# DSPclk.net
KiCad netlist of a schematic drawn in Altium Designer
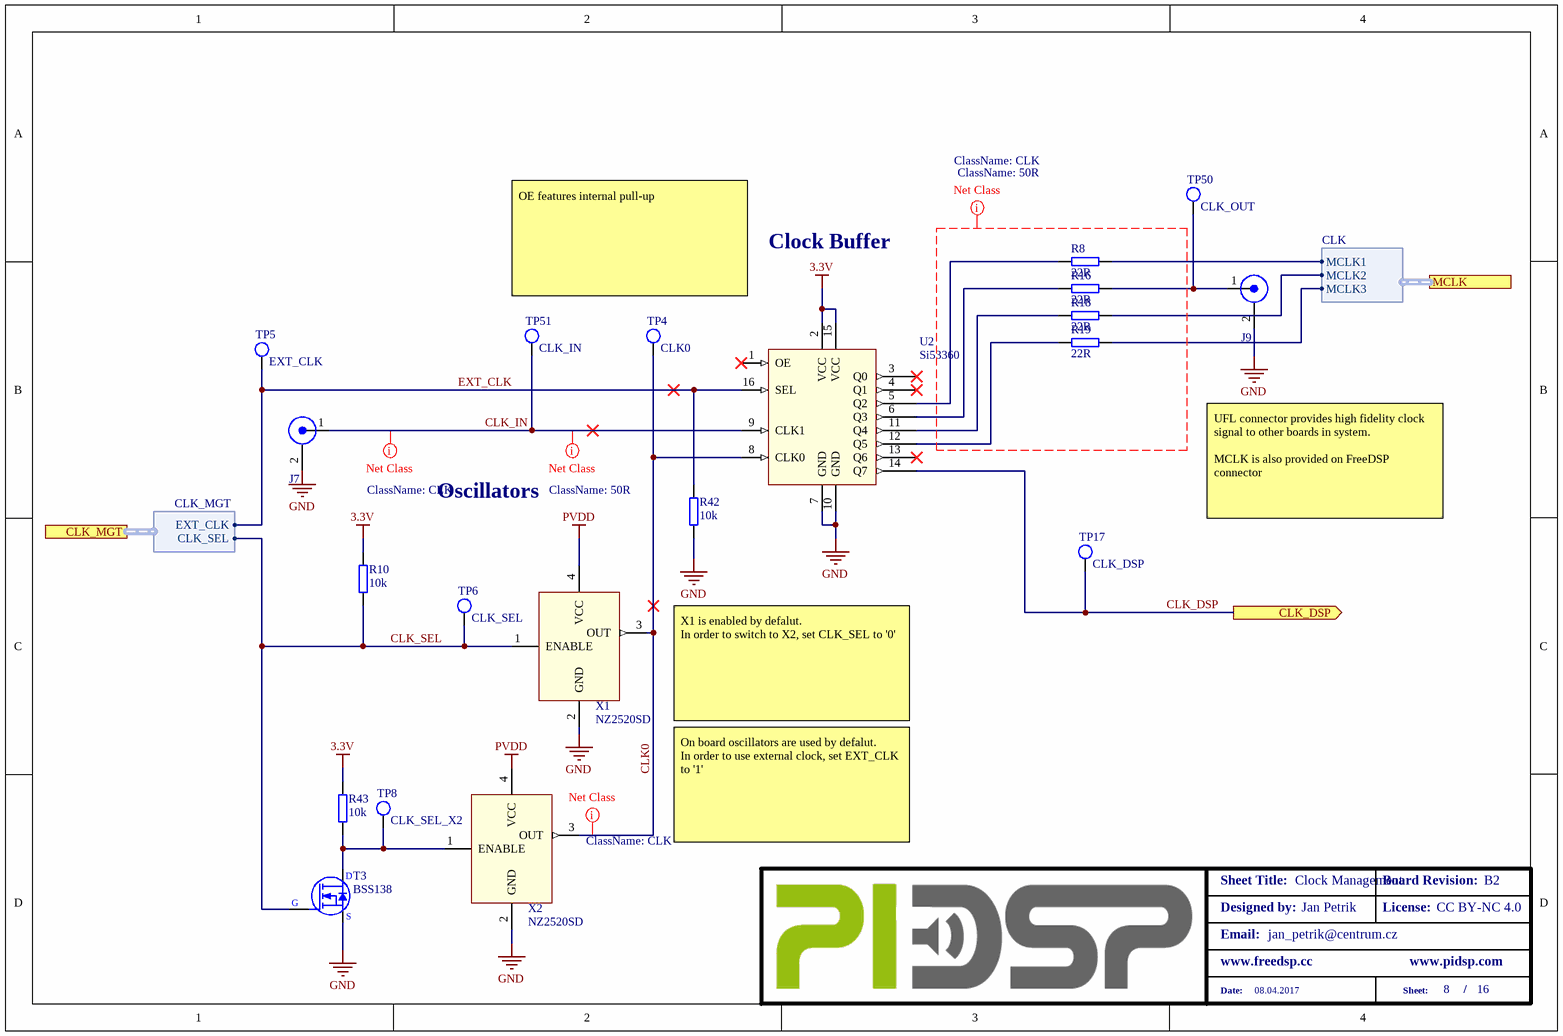
[diagram p0: DSPclk.SchDoc]

(export (version "E")
  (design (tool "Eeschema 10.0.6"))
  (components
    (comp (ref "J7")
      (value "CLK_IN")
      (footprint "U.FL-R-SMT")
      (description "Subminiature connector")
      (libsource (lib "JP_CONN") (part "UFL"))
    )
    (comp (ref "J9")
      (value "CLK_OUT")
      (footprint "U.FL-R-SMT")
      (description "Subminiature connector")
      (libsource (lib "JP_CONN") (part "UFL"))
    )
    (comp (ref "R8")
      (value "22R")
      (footprint "RESC1608X06N(SMR0603)")
      (description "Chip Resistor")
      (fields (field (name "AUTHOR") "JP/10.06.2014"))
      (libsource (lib "JP_R") (part "22R-100mW-0603-ThickFilm"))
    )
    (comp (ref "R10")
      (value "10k")
      (footprint "RESC1608X06N(SMR0603)")
      (description "Chip Resistor")
      (fields (field (name "AUTHOR") "JP/10.06.2014"))
      (libsource (lib "JP_R") (part "10k-100mW-0603-ThickFilm"))
    )
    (comp (ref "R16")
      (value "22R")
      (footprint "RESC1608X06N(SMR0603)")
      (description "Chip Resistor")
      (fields (field (name "AUTHOR") "JP/10.06.2014"))
      (libsource (lib "JP_R") (part "22R-100mW-0603-ThickFilm"))
    )
    (comp (ref "R18")
      (value "22R")
      (footprint "RESC1608X06N(SMR0603)")
      (description "Chip Resistor")
      (fields (field (name "AUTHOR") "JP/10.06.2014"))
      (libsource (lib "JP_R") (part "22R-100mW-0603-ThickFilm"))
    )
    (comp (ref "R19")
      (value "22R")
      (footprint "RESC1608X06N(SMR0603)")
      (description "Chip Resistor")
      (fields (field (name "AUTHOR") "JP/10.06.2014"))
      (libsource (lib "JP_R") (part "22R-100mW-0603-ThickFilm"))
    )
    (comp (ref "R42")
      (value "10k")
      (footprint "RESC1608X06N(SMR0603)")
      (description "Chip Resistor")
      (fields (field (name "AUTHOR") "JP/10.06.2014"))
      (libsource (lib "JP_R") (part "10k-100mW-0603-ThickFilm"))
    )
    (comp (ref "R43")
      (value "10k")
      (footprint "RESC1608X06N(SMR0603)")
      (description "Chip Resistor")
      (fields (field (name "AUTHOR") "JP/10.06.2014"))
      (libsource (lib "JP_R") (part "10k-100mW-0603-ThickFilm"))
    )
    (comp (ref "T3")
      (value "BSS138")
      (footprint "SOT95P230X110-3N(SOT23)")
      (description "N-MOSFET, Logic Level, 50V/0,22A/3.5Ohm")
      (fields (field (name "AUTHOR") "JM 2.7.2014"))
      (libsource (lib "JP_IC") (part "ET+BSS138XX0"))
    )
    (comp (ref "TP4")
      (value "CLK0")
      (footprint "TP_0.8/0.4_ROUND")
      (description "Testpoint - VIA")
      (libsource (lib "JP_CONN") (part "TEST_POINT_VIA"))
    )
    (comp (ref "TP5")
      (value "EXT_CLK")
      (footprint "TP_0.8/0.4_ROUND")
      (description "Testpoint - VIA")
      (libsource (lib "JP_CONN") (part "TEST_POINT_VIA"))
    )
    (comp (ref "TP6")
      (value "CLK_SEL")
      (footprint "TP_0.8/0.4_ROUND")
      (description "Testpoint - VIA")
      (libsource (lib "JP_CONN") (part "TEST_POINT_VIA"))
    )
    (comp (ref "TP8")
      (value "CLK_SEL_X2")
      (footprint "TP_0.8/0.4_ROUND")
      (description "Testpoint - VIA")
      (libsource (lib "JP_CONN") (part "TEST_POINT_VIA"))
    )
    (comp (ref "TP17")
      (value "CLK_DSP")
      (footprint "TP_0.8/0.4_ROUND")
      (description "Testpoint - VIA")
      (libsource (lib "JP_CONN") (part "TEST_POINT_VIA"))
    )
    (comp (ref "TP50")
      (value "CLK_OUT")
      (footprint "TP_0.8/0.4_ROUND")
      (description "Testpoint - VIA")
      (libsource (lib "JP_CONN") (part "TEST_POINT_VIA"))
    )
    (comp (ref "TP51")
      (value "CLK_IN")
      (footprint "TP_0.8/0.4_ROUND")
      (description "Testpoint - VIA")
      (libsource (lib "JP_CONN") (part "TEST_POINT_VIA"))
    )
    (comp (ref "U2")
      (value "Si53360")
      (footprint "TSOP65P640X120-16N (TSSOP16-4.4MM)")
      (description "1:8 LOW JITTER CMOS CLOCK BUFFER  WITH 2:1 INPUT MUX")
      (libsource (lib "JP_IC") (part "Si53360"))
    )
    (comp (ref "X1")
      (value "NZ2520SD")
      (footprint "2.5x2mm osclillator")
      (description "Low Phase Noise Oscillator")
      (libsource (lib "IC") (part "NZ2520SD"))
    )
    (comp (ref "X2")
      (value "NZ2520SD")
      (footprint "2.5x2mm osclillator")
      (description "Low Phase Noise Oscillator")
      (libsource (lib "IC") (part "NZ2520SD"))
    )
  )
  (nets
    (net (code "3") (name "/CLK0") (class "Default")
      (node (ref "TP4") (pin "1") (pintype "passive"))
      (node (ref "U2") (pin "8") (pinfunction "CLK0_8") (pintype "input"))
      (node (ref "X1") (pin "3") (pinfunction "OUT_3") (pintype "output"))
      (node (ref "X2") (pin "3") (pinfunction "OUT_3") (pintype "output"))
    )
    (net (code "4") (name "/CLK_DSP") (class "Default")
      (node (ref "TP17") (pin "1") (pintype "passive"))
      (node (ref "U2") (pin "14") (pinfunction "Q7_14") (pintype "output"))
    )
    (net (code "5") (name "/CLK_IN") (class "Default")
      (node (ref "J7") (pin "1") (pinfunction "Signal_1") (pintype "passive"))
      (node (ref "TP51") (pin "1") (pintype "passive"))
      (node (ref "U2") (pin "9") (pinfunction "CLK1_9") (pintype "input"))
    )
    (net (code "6") (name "/CLK_SEL") (class "Default")
      (node (ref "R10") (pin "1") (pinfunction "1_1") (pintype "passive"))
      (node (ref "T3") (pin "1") (pinfunction "G_1") (pintype "passive"))
      (node (ref "TP6") (pin "1") (pintype "passive"))
      (node (ref "X1") (pin "1") (pinfunction "ENABLE_1") (pintype "passive"))
    )
    (net (code "7") (name "/EXT_CLK") (class "Default")
      (node (ref "R42") (pin "2") (pinfunction "2_2") (pintype "passive"))
      (node (ref "TP5") (pin "1") (pintype "passive"))
      (node (ref "U2") (pin "16") (pinfunction "SEL_16") (pintype "input"))
    )
    (net (code "8") (name "/MCLK1") (class "Default")
      (node (ref "R8") (pin "2") (pinfunction "2_2") (pintype "passive"))
    )
    (net (code "9") (name "/MCLK2") (class "Default")
      (node (ref "R18") (pin "2") (pinfunction "2_2") (pintype "passive"))
    )
    (net (code "10") (name "/MCLK3") (class "Default")
      (node (ref "R19") (pin "2") (pinfunction "2_2") (pintype "passive"))
    )
    (net (code "13") (name "3.3V") (class "Default")
      (node (ref "R10") (pin "2") (pinfunction "2_2") (pintype "passive"))
      (node (ref "R43") (pin "2") (pinfunction "2_2") (pintype "passive"))
      (node (ref "U2") (pin "15") (pinfunction "VCC_15") (pintype "power_in"))
      (node (ref "U2") (pin "2") (pinfunction "VCC_2") (pintype "power_in"))
    )
    (net (code "14") (name "GND") (class "Default")
      (node (ref "J7") (pin "2") (pinfunction "GND_2") (pintype "passive"))
      (node (ref "J9") (pin "2") (pinfunction "GND_2") (pintype "passive"))
      (node (ref "R42") (pin "1") (pinfunction "1_1") (pintype "passive"))
      (node (ref "T3") (pin "2") (pinfunction "S_2") (pintype "passive"))
      (node (ref "U2") (pin "10") (pinfunction "GND_10") (pintype "power_in"))
      (node (ref "U2") (pin "7") (pinfunction "GND_7") (pintype "power_in"))
      (node (ref "X1") (pin "2") (pinfunction "GND_2") (pintype "passive"))
      (node (ref "X2") (pin "2") (pinfunction "GND_2") (pintype "passive"))
    )
    (net (code "15") (name "Net-(J9-Signal)") (class "Default")
      (node (ref "J9") (pin "1") (pinfunction "Signal_1") (pintype "passive"))
      (node (ref "R16") (pin "2") (pinfunction "2_2") (pintype "passive"))
      (node (ref "TP50") (pin "1") (pintype "passive"))
    )
    (net (code "16") (name "Net-(T3-D)") (class "Default")
      (node (ref "R43") (pin "1") (pinfunction "1_1") (pintype "passive"))
      (node (ref "T3") (pin "3") (pinfunction "D_3") (pintype "passive"))
      (node (ref "TP8") (pin "1") (pintype "passive"))
      (node (ref "X2") (pin "1") (pinfunction "ENABLE_1") (pintype "passive"))
    )
    (net (code "17") (name "Net-(U2-Q2)") (class "Default")
      (node (ref "R8") (pin "1") (pinfunction "1_1") (pintype "passive"))
      (node (ref "U2") (pin "5") (pinfunction "Q2_5") (pintype "output"))
    )
    (net (code "18") (name "Net-(U2-Q3)") (class "Default")
      (node (ref "R16") (pin "1") (pinfunction "1_1") (pintype "passive"))
      (node (ref "U2") (pin "6") (pinfunction "Q3_6") (pintype "output"))
    )
    (net (code "19") (name "Net-(U2-Q4)") (class "Default")
      (node (ref "R18") (pin "1") (pinfunction "1_1") (pintype "passive"))
      (node (ref "U2") (pin "11") (pinfunction "Q4_11") (pintype "output"))
    )
    (net (code "20") (name "Net-(U2-Q5)") (class "Default")
      (node (ref "R19") (pin "1") (pinfunction "1_1") (pintype "passive"))
      (node (ref "U2") (pin "12") (pinfunction "Q5_12") (pintype "output"))
    )
    (net (code "21") (name "PVDD") (class "Default")
      (node (ref "X1") (pin "4") (pinfunction "VCC_4") (pintype "passive"))
      (node (ref "X2") (pin "4") (pinfunction "VCC_4") (pintype "passive"))
    )
    (net (code "22") (name "unconnected-(U2-OE-Pad1)") (class "Default")
      (node (ref "U2") (pin "1") (pinfunction "OE_1") (pintype "input+no_connect"))
    )
    (net (code "23") (name "unconnected-(U2-Q0-Pad3)") (class "Default")
      (node (ref "U2") (pin "3") (pinfunction "Q0_3") (pintype "output+no_connect"))
    )
    (net (code "24") (name "unconnected-(U2-Q1-Pad4)") (class "Default")
      (node (ref "U2") (pin "4") (pinfunction "Q1_4") (pintype "output+no_connect"))
    )
    (net (code "25") (name "unconnected-(U2-Q6-Pad13)") (class "Default")
      (node (ref "U2") (pin "13") (pinfunction "Q6_13") (pintype "output+no_connect"))
    )
  )
)
